# cpu.net
KiCad netlist of a schematic drawn in Altium Designer
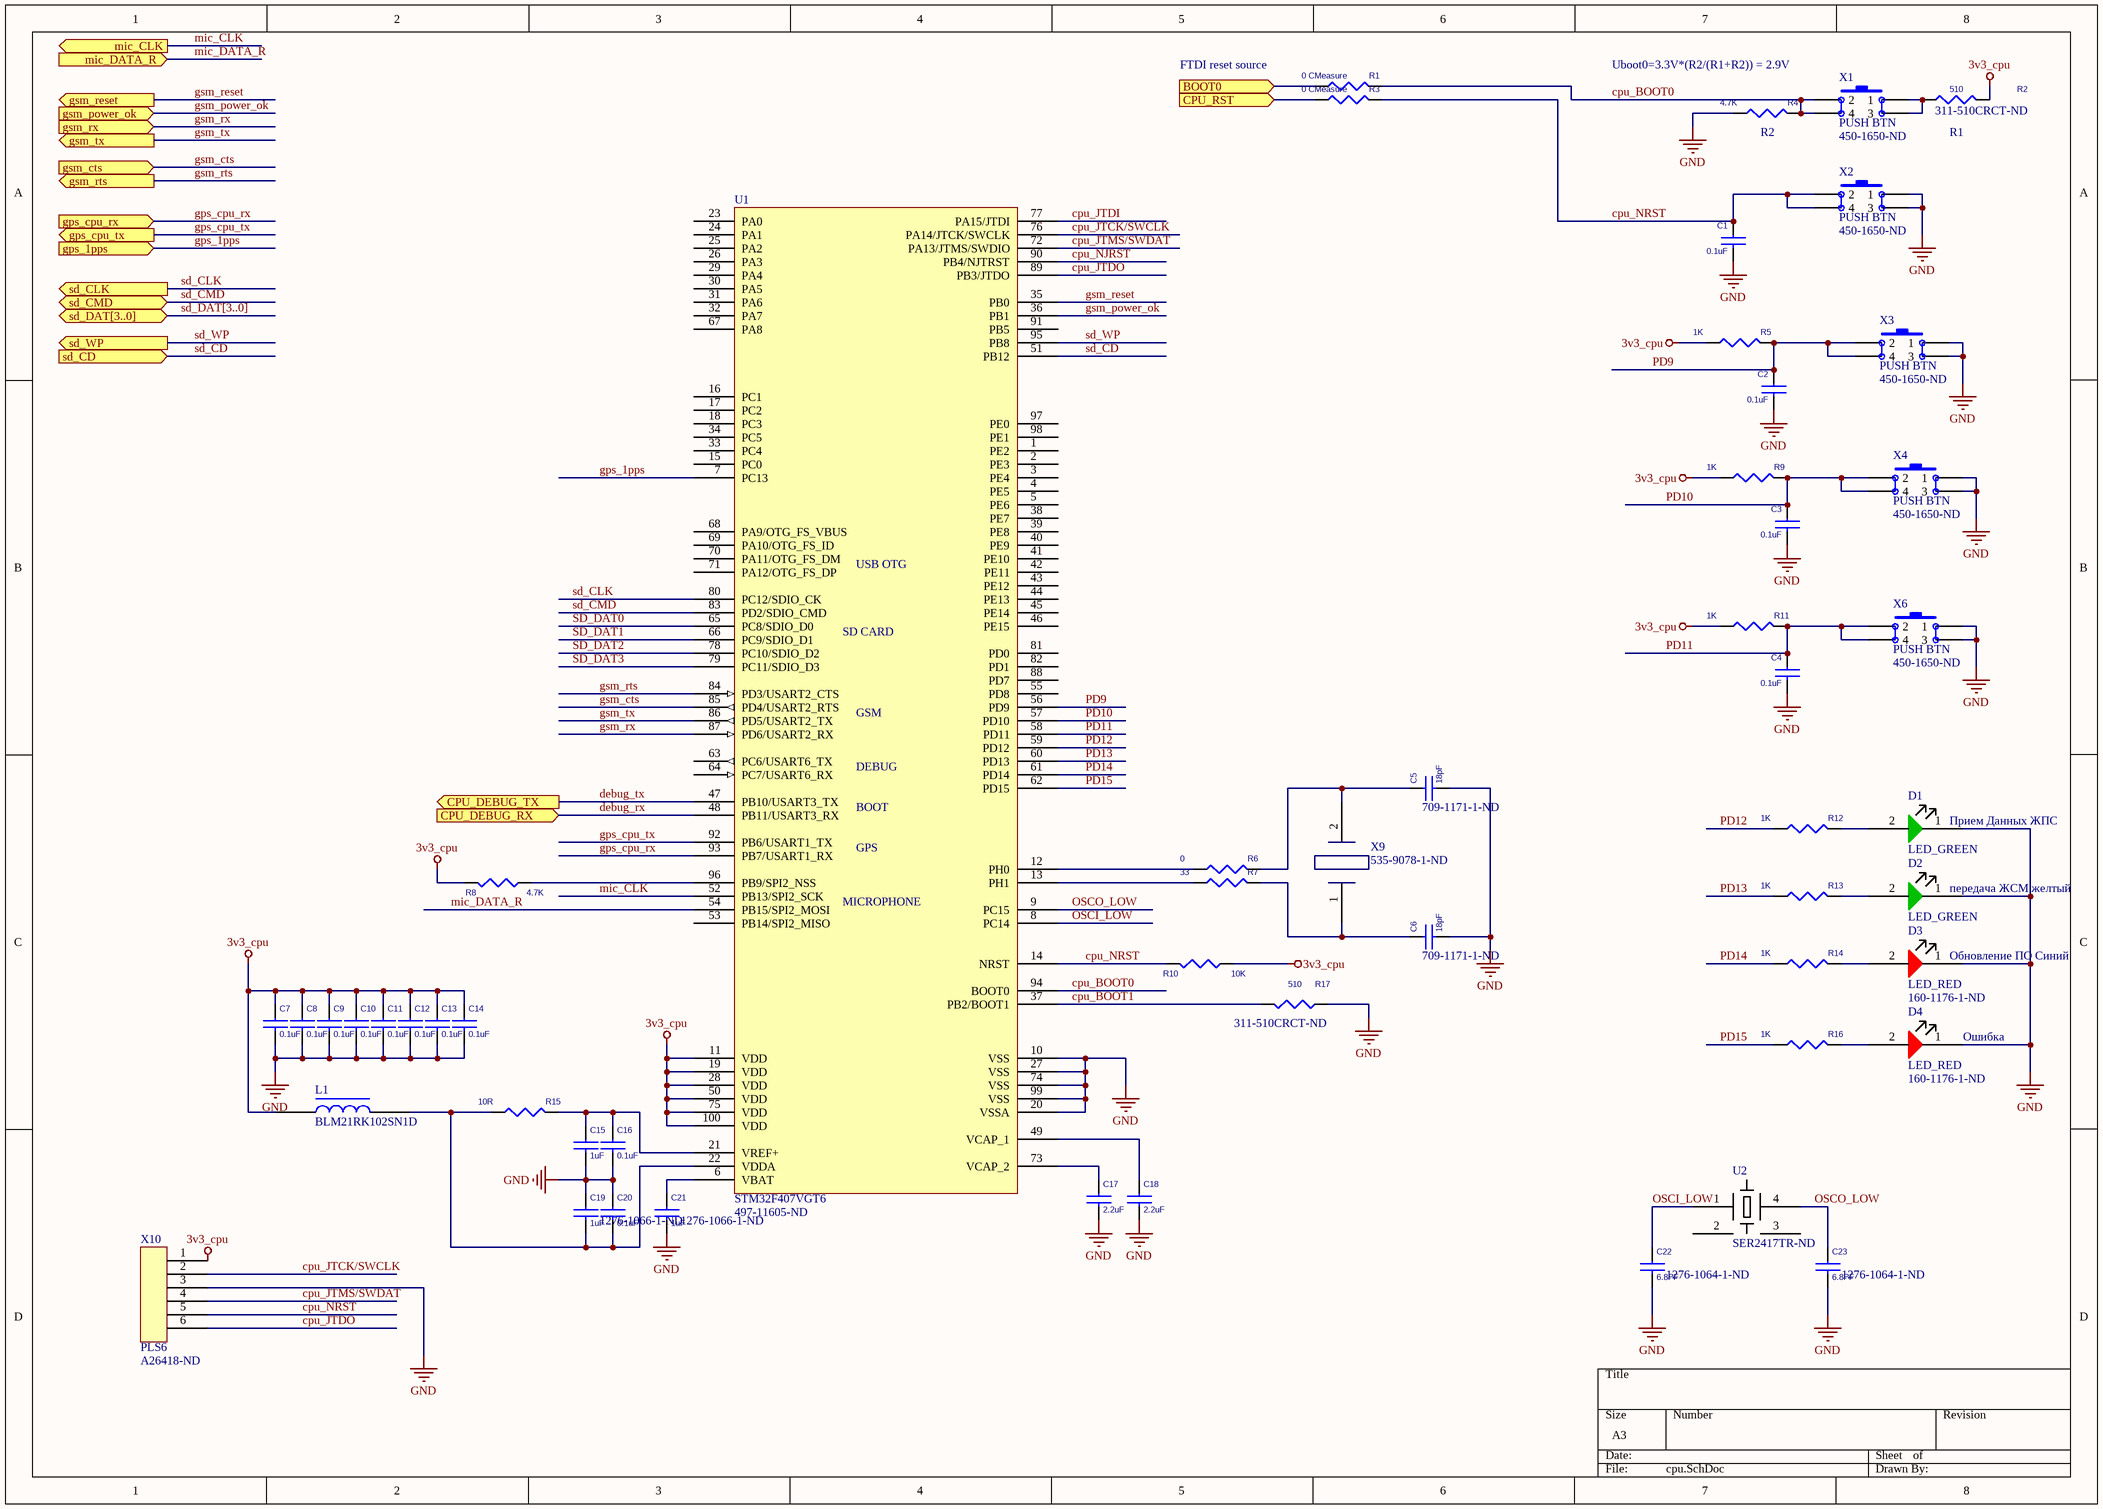
[diagram p0: cpu.SchDoc]

(export (version "E")
  (design (tool "Eeschema 10.0.6"))
  (components
    (comp (ref "C1")
      (value "0.1uF")
      (footprint "CAPC2012X09M")
      (description "CAP CER 0.1UF 25V 10% X7R 0805")
      (libsource (lib "Capacitors") (part "CAP_SMD_0.1UF_10%"))
    )
    (comp (ref "C2")
      (value "0.1uF")
      (footprint "CAPC2012X09M")
      (description "CAP CER 0.1UF 25V 10% X7R 0805")
      (libsource (lib "Capacitors") (part "CAP_SMD_0.1UF_10%"))
    )
    (comp (ref "C3")
      (value "0.1uF")
      (footprint "CAPC2012X09M")
      (description "CAP CER 0.1UF 25V 10% X7R 0805")
      (libsource (lib "Capacitors") (part "CAP_SMD_0.1UF_10%"))
    )
    (comp (ref "C4")
      (value "0.1uF")
      (footprint "CAPC2012X09M")
      (description "CAP CER 0.1UF 25V 10% X7R 0805")
      (libsource (lib "Capacitors") (part "CAP_SMD_0.1UF_10%"))
    )
    (comp (ref "C5")
      (value "18pF")
      (footprint "CAPC2012X09M")
      (description "CAP CER 27PF 200V 5% NP0 0805")
      (fields (field (name "SUPPLIER PART NUMBER 1") "709-1171-1-ND"))
      (libsource (lib "Capacitors") (part "CAP_SMD_18PF_5%"))
    )
    (comp (ref "C6")
      (value "18pF")
      (footprint "CAPC2012X09M")
      (description "CAP CER 27PF 200V 5% NP0 0805")
      (fields (field (name "SUPPLIER PART NUMBER 1") "709-1171-1-ND"))
      (libsource (lib "Capacitors") (part "CAP_SMD_18PF_5%"))
    )
    (comp (ref "C7")
      (value "0.1uF")
      (footprint "CAPC2012X09M")
      (description "CAP CER 0.1UF 25V 10% X7R 0805")
      (libsource (lib "Capacitors") (part "CAP_SMD_0.1UF_10%"))
    )
    (comp (ref "C8")
      (value "0.1uF")
      (footprint "CAPC2012X09M")
      (description "CAP CER 0.1UF 25V 10% X7R 0805")
      (libsource (lib "Capacitors") (part "CAP_SMD_0.1UF_10%"))
    )
    (comp (ref "C9")
      (value "0.1uF")
      (footprint "CAPC2012X09M")
      (description "CAP CER 0.1UF 25V 10% X7R 0805")
      (libsource (lib "Capacitors") (part "CAP_SMD_0.1UF_10%"))
    )
    (comp (ref "C10")
      (value "0.1uF")
      (footprint "CAPC2012X09M")
      (description "CAP CER 0.1UF 25V 10% X7R 0805")
      (libsource (lib "Capacitors") (part "CAP_SMD_0.1UF_10%"))
    )
    (comp (ref "C11")
      (value "0.1uF")
      (footprint "CAPC2012X09M")
      (description "CAP CER 0.1UF 25V 10% X7R 0805")
      (libsource (lib "Capacitors") (part "CAP_SMD_0.1UF_10%"))
    )
    (comp (ref "C12")
      (value "0.1uF")
      (footprint "CAPC2012X09M")
      (description "CAP CER 0.1UF 25V 10% X7R 0805")
      (libsource (lib "Capacitors") (part "CAP_SMD_0.1UF_10%"))
    )
    (comp (ref "C13")
      (value "0.1uF")
      (footprint "CAPC2012X09M")
      (description "CAP CER 0.1UF 25V 10% X7R 0805")
      (libsource (lib "Capacitors") (part "CAP_SMD_0.1UF_10%"))
    )
    (comp (ref "C14")
      (value "0.1uF")
      (footprint "CAPC2012X09M")
      (description "CAP CER 0.1UF 25V 10% X7R 0805")
      (libsource (lib "Capacitors") (part "CAP_SMD_0.1UF_10%"))
    )
    (comp (ref "C15")
      (value "1uF")
      (footprint "CAPC2012X09M")
      (description "MLCC; 1uF; 25V; X7R; ±10%; SMD; 0805;")
      (libsource (lib "Capacitors") (part "CAP_SMD_1uF_10%"))
    )
    (comp (ref "C16")
      (value "0.1uF")
      (footprint "CAPC2012X09M")
      (description "CAP CER 0.1UF 25V 10% X7R 0805")
      (libsource (lib "Capacitors") (part "CAP_SMD_0.1UF_10%"))
    )
    (comp (ref "C17")
      (value "2.2uF")
      (footprint "CAPC2012X09M")
      (description "CAP CER 2.2UF 16V 10% X5R 0805")
      (libsource (lib "Capacitors") (part "CAP_SMD_2.2uF_10%"))
    )
    (comp (ref "C18")
      (value "2.2uF")
      (footprint "CAPC2012X09M")
      (description "CAP CER 2.2UF 16V 10% X5R 0805")
      (libsource (lib "Capacitors") (part "CAP_SMD_2.2uF_10%"))
    )
    (comp (ref "C19")
      (value "1uF")
      (footprint "CAPC2012X09M")
      (description "MLCC; 1uF; 25V; X7R; ±10%; SMD; 0805;")
      (fields (field (name "SUPPLIER PART NUMBER 1") "1276-1066-1-ND"))
      (libsource (lib "Capacitors") (part "CAP_SMD_1uF_10%"))
    )
    (comp (ref "C20")
      (value "0.1uF")
      (footprint "CAPC2012X09M")
      (description "CAP CER 0.1UF 25V 10% X7R 0805")
      (libsource (lib "Capacitors") (part "CAP_SMD_0.1UF_10%"))
    )
    (comp (ref "C21")
      (value "1uF")
      (footprint "CAPC2012X09M")
      (description "MLCC; 1uF; 25V; X7R; ±10%; SMD; 0805;")
      (fields (field (name "SUPPLIER PART NUMBER 1") "1276-1066-1-ND"))
      (libsource (lib "Capacitors") (part "CAP_SMD_1uF_10%"))
    )
    (comp (ref "C22")
      (value "6.8PF")
      (footprint "CAPC2012X09M")
      (description "CAP MLCC 6.8PF 50V 5% NP0 0805")
      (fields (field (name "SUPPLIER PART NUMBER 1") "1276-1064-1-ND"))
      (libsource (lib "Capacitors") (part "CAP_SMD_6.8PF_5%"))
    )
    (comp (ref "C23")
      (value "6.8PF")
      (footprint "CAPC2012X09M")
      (description "CAP MLCC 6.8PF 50V 5% NP0 0805")
      (fields (field (name "SUPPLIER PART NUMBER 1") "1276-1064-1-ND"))
      (libsource (lib "Capacitors") (part "CAP_SMD_6.8PF_5%"))
    )
    (comp (ref "D1")
      (value "LED_GREEN")
      (footprint "DIOC2012X11N")
      (libsource (lib "Passive") (part "LED_GREEN"))
    )
    (comp (ref "D2")
      (value "LED_GREEN")
      (footprint "DIOC2012X11N")
      (libsource (lib "Passive") (part "LED_GREEN"))
    )
    (comp (ref "D3")
      (value "LED_RED")
      (footprint "DIOC2012X11N")
      (fields (field (name "SUPPLIER PART NUMBER 1") "160-1176-1-ND"))
      (libsource (lib "Passive") (part "LED_RED"))
    )
    (comp (ref "D4")
      (value "LED_RED")
      (footprint "DIOC2012X11N")
      (fields (field (name "SUPPLIER PART NUMBER 1") "160-1176-1-ND"))
      (libsource (lib "Passive") (part "LED_RED"))
    )
    (comp (ref "L1")
      (value "BLM21RK102SN1D")
      (footprint "DIOC2012X11N")
      (libsource (lib "Passive") (part "BLM21RK102SN1D"))
    )
    (comp (ref "R1")
      (value "0 CMeasure")
      (footprint "RESC2013X06M_CMEASURE")
      (description "RES 0.0 OHM 1/8W JUMP 0805 SMD")
      (libsource (lib "Resistors") (part "RES_SMD_0_CURRENT"))
    )
    (comp (ref "R2")
      (value "510")
      (footprint "RESC2013X06M")
      (description "RES - 510 OHM, 5%, 1/8W, 0805 SMD")
      (fields (field (name "SUPPLIER PART NUMBER 1") "311-510CRCT-ND"))
      (libsource (lib "Resistors") (part "RES_SMD_510_5%"))
    )
    (comp (ref "R3")
      (value "0 CMeasure")
      (footprint "RESC2013X06M_CMEASURE")
      (description "RES 0.0 OHM 1/8W JUMP 0805 SMD")
      (libsource (lib "Resistors") (part "RES_SMD_0_CURRENT"))
    )
    (comp (ref "R4")
      (value "4.7K")
      (footprint "RESC2013X06M")
      (description "RES 4.7K OHM 1/8W 1% 0805 SMD")
      (libsource (lib "Resistors") (part "RES_SMD_4.7K_1%"))
    )
    (comp (ref "R5")
      (value "1K")
      (footprint "RESC2013X06M")
      (description "RES - 1K OHM, 5%, 1/8W, 0805 SMD")
      (libsource (lib "Resistors") (part "RES_SMD_1K_5%"))
    )
    (comp (ref "R6")
      (value "0")
      (footprint "RESC2013X06M")
      (description "RES 0.0 OHM 1/8W JUMP 0805 SMD")
      (libsource (lib "Resistors") (part "RES_SMD_0"))
    )
    (comp (ref "R7")
      (value "33")
      (footprint "RESC2013X06M")
      (description "RES - 33 OHM, 5%, 1/8W, 0805 SMD")
      (libsource (lib "Resistors") (part "RES_SMD_33R_5%"))
    )
    (comp (ref "R8")
      (value "4.7K")
      (footprint "RESC2013X06M")
      (description "RES 4.7K OHM 1/8W 1% 0805 SMD")
      (libsource (lib "Resistors") (part "RES_SMD_4.7K_1%"))
    )
    (comp (ref "R9")
      (value "1K")
      (footprint "RESC2013X06M")
      (description "RES - 1K OHM, 5%, 1/8W, 0805 SMD")
      (libsource (lib "Resistors") (part "RES_SMD_1K_5%"))
    )
    (comp (ref "R10")
      (value "10K")
      (footprint "RESC2013X06M")
      (description "RES 10K OHM 1/8W 5% 0805 SMD")
      (libsource (lib "Resistors") (part "RES_SMD_10K_5%"))
    )
    (comp (ref "R11")
      (value "1K")
      (footprint "RESC2013X06M")
      (description "RES - 1K OHM, 5%, 1/8W, 0805 SMD")
      (libsource (lib "Resistors") (part "RES_SMD_1K_5%"))
    )
    (comp (ref "R12")
      (value "1K")
      (footprint "RESC2013X06M")
      (description "RES - 1K OHM, 5%, 1/8W, 0805 SMD")
      (libsource (lib "Resistors") (part "RES_SMD_1K_5%"))
    )
    (comp (ref "R13")
      (value "1K")
      (footprint "RESC2013X06M")
      (description "RES - 1K OHM, 5%, 1/8W, 0805 SMD")
      (libsource (lib "Resistors") (part "RES_SMD_1K_5%"))
    )
    (comp (ref "R14")
      (value "1K")
      (footprint "RESC2013X06M")
      (description "RES - 1K OHM, 5%, 1/8W, 0805 SMD")
      (libsource (lib "Resistors") (part "RES_SMD_1K_5%"))
    )
    (comp (ref "R15")
      (value "10R")
      (footprint "RESC2013X06M")
      (description "RES 10 OHM 1/8W 1% 0805 SMD")
      (libsource (lib "Resistors") (part "RES_SMD_10R_5%"))
    )
    (comp (ref "R16")
      (value "1K")
      (footprint "RESC2013X06M")
      (description "RES - 1K OHM, 5%, 1/8W, 0805 SMD")
      (libsource (lib "Resistors") (part "RES_SMD_1K_5%"))
    )
    (comp (ref "R17")
      (value "510")
      (footprint "RESC2013X06M")
      (description "RES - 510 OHM, 5%, 1/8W, 0805 SMD")
      (fields (field (name "SUPPLIER PART NUMBER 1") "311-510CRCT-ND"))
      (libsource (lib "Resistors") (part "RES_SMD_510_5%"))
    )
    (comp (ref "U1")
      (value "STM32F407VGT6")
      (footprint "TSQFP50P1600X1600X160-100M")
      (fields (field (name "SUPPLIER PART NUMBER 1") "497-11605-ND"))
      (libsource (lib "TruthEar") (part "STM32F407VGT6"))
    )
    (comp (ref "U2")
      (value "32.768KHZ")
      (footprint "SOJ550P380X254-4M")
      (fields (field (name "SUPPLIER PART NUMBER 1") "SER2417TR-ND"))
      (libsource (lib "TruthEar") (part "MC-306"))
    )
    (comp (ref "X1")
      (value "PUSH BTN")
      (footprint "PUSHBTN")
      (fields (field (name "SUPPLIER PART NUMBER 1") "450-1650-ND"))
      (libsource (lib "TruthEar") (part "SW1"))
    )
    (comp (ref "X2")
      (value "PUSH BTN")
      (footprint "PUSHBTN")
      (fields (field (name "SUPPLIER PART NUMBER 1") "450-1650-ND"))
      (libsource (lib "TruthEar") (part "SW1"))
    )
    (comp (ref "X3")
      (value "PUSH BTN")
      (footprint "PUSHBTN")
      (fields (field (name "SUPPLIER PART NUMBER 1") "450-1650-ND"))
      (libsource (lib "TruthEar") (part "SW1"))
    )
    (comp (ref "X4")
      (value "PUSH BTN")
      (footprint "PUSHBTN")
      (fields (field (name "SUPPLIER PART NUMBER 1") "450-1650-ND"))
      (libsource (lib "TruthEar") (part "SW1"))
    )
    (comp (ref "X6")
      (value "PUSH BTN")
      (footprint "PUSHBTN")
      (fields (field (name "SUPPLIER PART NUMBER 1") "450-1650-ND"))
      (libsource (lib "TruthEar") (part "SW1"))
    )
    (comp (ref "X9")
      (value "25.000Mhz")
      (footprint "SODFL1270X420-2L")
      (fields (field (name "SUPPLIER PART NUMBER 1") "535-9078-1-ND"))
      (libsource (lib "TruthEar") (part "OSC25M"))
    )
    (comp (ref "X10")
      (value "PLS6")
      (footprint "PLS6")
      (fields (field (name "SUPPLIER PART NUMBER 1") "A26418-ND"))
      (libsource (lib "Connectors") (part "PLS6"))
    )
  )
  (nets
    (net (code "5") (name "/BOOT0") (class "Default")
      (node (ref "R1") (pin "1") (pinfunction "1_1") (pintype "passive"))
    )
    (net (code "6") (name "/CPU_RST") (class "Default")
      (node (ref "R3") (pin "1") (pinfunction "1_1") (pintype "passive"))
    )
    (net (code "7") (name "/OSCI_LOW") (class "Default")
      (node (ref "C22") (pin "1") (pinfunction "1_1") (pintype "passive"))
      (node (ref "U1") (pin "8") (pinfunction "PC14_8") (pintype "passive"))
      (node (ref "U2") (pin "1") (pinfunction "OSC1_1") (pintype "power_in"))
    )
    (net (code "8") (name "/OSCO_LOW") (class "Default")
      (node (ref "C23") (pin "1") (pinfunction "1_1") (pintype "passive"))
      (node (ref "U1") (pin "9") (pinfunction "PC15_9") (pintype "passive"))
      (node (ref "U2") (pin "4") (pinfunction "OSC2_4") (pintype "power_in"))
    )
    (net (code "9") (name "/PD9") (class "Default")
      (node (ref "C2") (pin "1") (pinfunction "1_1") (pintype "passive"))
      (node (ref "R5") (pin "2") (pinfunction "2_2") (pintype "passive"))
      (node (ref "U1") (pin "56") (pinfunction "PD9_56") (pintype "passive"))
      (node (ref "X3") (pin "2") (pinfunction "2_2") (pintype "passive"))
      (node (ref "X3") (pin "4") (pinfunction "4_4") (pintype "passive"))
    )
    (net (code "10") (name "/PD10") (class "Default")
      (node (ref "C3") (pin "1") (pinfunction "1_1") (pintype "passive"))
      (node (ref "R9") (pin "2") (pinfunction "2_2") (pintype "passive"))
      (node (ref "U1") (pin "57") (pinfunction "PD10_57") (pintype "passive"))
      (node (ref "X4") (pin "2") (pinfunction "2_2") (pintype "passive"))
      (node (ref "X4") (pin "4") (pinfunction "4_4") (pintype "passive"))
    )
    (net (code "11") (name "/PD11") (class "Default")
      (node (ref "C4") (pin "1") (pinfunction "1_1") (pintype "passive"))
      (node (ref "R11") (pin "2") (pinfunction "2_2") (pintype "passive"))
      (node (ref "U1") (pin "58") (pinfunction "PD11_58") (pintype "passive"))
      (node (ref "X6") (pin "2") (pinfunction "2_2") (pintype "passive"))
      (node (ref "X6") (pin "4") (pinfunction "4_4") (pintype "passive"))
    )
    (net (code "12") (name "/PD12") (class "Default")
      (node (ref "R12") (pin "1") (pinfunction "1_1") (pintype "passive"))
      (node (ref "U1") (pin "59") (pinfunction "PD12_59") (pintype "passive"))
    )
    (net (code "13") (name "/PD13") (class "Default")
      (node (ref "R13") (pin "1") (pinfunction "1_1") (pintype "passive"))
      (node (ref "U1") (pin "60") (pinfunction "PD13_60") (pintype "passive"))
    )
    (net (code "14") (name "/PD14") (class "Default")
      (node (ref "R14") (pin "1") (pinfunction "1_1") (pintype "passive"))
      (node (ref "U1") (pin "61") (pinfunction "PD14_61") (pintype "passive"))
    )
    (net (code "15") (name "/PD15") (class "Default")
      (node (ref "R16") (pin "1") (pinfunction "1_1") (pintype "passive"))
      (node (ref "U1") (pin "62") (pinfunction "PD15_62") (pintype "passive"))
    )
    (net (code "16") (name "/SD_DAT0") (class "Default")
      (node (ref "U1") (pin "65") (pinfunction "PC8/SDIO_D0_65") (pintype "passive"))
    )
    (net (code "17") (name "/SD_DAT1") (class "Default")
      (node (ref "U1") (pin "66") (pinfunction "PC9/SDIO_D1_66") (pintype "passive"))
    )
    (net (code "18") (name "/SD_DAT2") (class "Default")
      (node (ref "U1") (pin "78") (pinfunction "PC10/SDIO_D2_78") (pintype "passive"))
    )
    (net (code "19") (name "/SD_DAT3") (class "Default")
      (node (ref "U1") (pin "79") (pinfunction "PC11/SDIO_D3_79") (pintype "passive"))
    )
    (net (code "20") (name "/cpu_BOOT0") (class "Default")
      (node (ref "R1") (pin "2") (pinfunction "2_2") (pintype "passive"))
      (node (ref "R4") (pin "2") (pinfunction "2_2") (pintype "passive"))
      (node (ref "U1") (pin "94") (pinfunction "BOOT0_94") (pintype "passive"))
      (node (ref "X1") (pin "2") (pinfunction "2_2") (pintype "passive"))
      (node (ref "X1") (pin "4") (pinfunction "4_4") (pintype "passive"))
    )
    (net (code "21") (name "/cpu_BOOT1") (class "Default")
      (node (ref "R17") (pin "2") (pinfunction "2_2") (pintype "passive"))
      (node (ref "U1") (pin "37") (pinfunction "PB2/BOOT1_37") (pintype "passive"))
    )
    (net (code "22") (name "/cpu_JTCK{slash}SWCLK") (class "Default")
      (node (ref "U1") (pin "76") (pinfunction "PA14/JTCK/SWCLK_76") (pintype "passive"))
      (node (ref "X10") (pin "2") (pinfunction "2_2") (pintype "power_in"))
    )
    (net (code "23") (name "/cpu_JTDI") (class "Default")
      (node (ref "U1") (pin "77") (pinfunction "PA15/JTDI_77") (pintype "passive"))
    )
    (net (code "24") (name "/cpu_JTDO") (class "Default")
      (node (ref "U1") (pin "89") (pinfunction "PB3/JTDO_89") (pintype "passive"))
      (node (ref "X10") (pin "6") (pinfunction "6_6") (pintype "power_in"))
    )
    (net (code "25") (name "/cpu_JTMS{slash}SWDAT") (class "Default")
      (node (ref "U1") (pin "72") (pinfunction "PA13/JTMS/SWDIO_72") (pintype "passive"))
      (node (ref "X10") (pin "4") (pinfunction "4_4") (pintype "power_in"))
    )
    (net (code "26") (name "/cpu_NJRST") (class "Default")
      (node (ref "U1") (pin "90") (pinfunction "PB4/NJTRST_90") (pintype "passive"))
    )
    (net (code "27") (name "/cpu_NRST") (class "Default")
      (node (ref "C1") (pin "1") (pinfunction "1_1") (pintype "passive"))
      (node (ref "R10") (pin "2") (pinfunction "2_2") (pintype "passive"))
      (node (ref "R3") (pin "2") (pinfunction "2_2") (pintype "passive"))
      (node (ref "U1") (pin "14") (pinfunction "NRST_14") (pintype "passive"))
      (node (ref "X10") (pin "5") (pinfunction "5_5") (pintype "power_in"))
      (node (ref "X2") (pin "2") (pinfunction "2_2") (pintype "passive"))
      (node (ref "X2") (pin "4") (pinfunction "4_4") (pintype "passive"))
    )
    (net (code "28") (name "/debug_rx") (class "Default")
      (node (ref "U1") (pin "48") (pinfunction "PB11/USART3_RX_48") (pintype "passive"))
    )
    (net (code "29") (name "/debug_tx") (class "Default")
      (node (ref "U1") (pin "47") (pinfunction "PB10/USART3_TX_47") (pintype "passive"))
    )
    (net (code "30") (name "/gps_1pps") (class "Default")
      (node (ref "U1") (pin "7") (pinfunction "PC13_7") (pintype "passive"))
    )
    (net (code "31") (name "/gps_cpu_rx") (class "Default")
      (node (ref "U1") (pin "93") (pinfunction "PB7/USART1_RX_93") (pintype "passive"))
    )
    (net (code "32") (name "/gps_cpu_tx") (class "Default")
      (node (ref "U1") (pin "92") (pinfunction "PB6/USART1_TX_92") (pintype "passive"))
    )
    (net (code "33") (name "/gsm_cts") (class "Default")
      (node (ref "U1") (pin "85") (pinfunction "PD4/USART2_RTS_85") (pintype "output"))
    )
    (net (code "34") (name "/gsm_power_ok") (class "Default")
      (node (ref "U1") (pin "36") (pinfunction "PB1_36") (pintype "passive"))
    )
    (net (code "35") (name "/gsm_reset") (class "Default")
      (node (ref "U1") (pin "35") (pinfunction "PB0_35") (pintype "passive"))
    )
    (net (code "36") (name "/gsm_rts") (class "Default")
      (node (ref "U1") (pin "84") (pinfunction "PD3/USART2_CTS_84") (pintype "input"))
    )
    (net (code "37") (name "/gsm_rx") (class "Default")
      (node (ref "U1") (pin "87") (pinfunction "PD6/USART2_RX_87") (pintype "input"))
    )
    (net (code "38") (name "/gsm_tx") (class "Default")
      (node (ref "U1") (pin "86") (pinfunction "PD5/USART2_TX_86") (pintype "output"))
    )
    (net (code "39") (name "/mic_CLK") (class "Default")
      (node (ref "U1") (pin "52") (pinfunction "PB13/SPI2_SCK_52") (pintype "passive"))
    )
    (net (code "40") (name "/mic_DATA_R") (class "Default")
      (node (ref "U1") (pin "54") (pinfunction "PB15/SPI2_MOSI_54") (pintype "passive"))
    )
    (net (code "41") (name "/sd_CD") (class "Default")
      (node (ref "U1") (pin "51") (pinfunction "PB12_51") (pintype "passive"))
    )
    (net (code "42") (name "/sd_CLK") (class "Default")
      (node (ref "U1") (pin "80") (pinfunction "PC12/SDIO_CK_80") (pintype "passive"))
    )
    (net (code "43") (name "/sd_CMD") (class "Default")
      (node (ref "U1") (pin "83") (pinfunction "PD2/SDIO_CMD_83") (pintype "passive"))
    )
    (net (code "45") (name "/sd_WP") (class "Default")
      (node (ref "U1") (pin "95") (pinfunction "PB8_95") (pintype "passive"))
    )
    (net (code "46") (name "3v3_cpu") (class "Default")
      (node (ref "C10") (pin "1") (pinfunction "1_1") (pintype "passive"))
      (node (ref "C11") (pin "1") (pinfunction "1_1") (pintype "passive"))
      (node (ref "C12") (pin "1") (pinfunction "1_1") (pintype "passive"))
      (node (ref "C13") (pin "1") (pinfunction "1_1") (pintype "passive"))
      (node (ref "C14") (pin "1") (pinfunction "1_1") (pintype "passive"))
      (node (ref "C7") (pin "1") (pinfunction "1_1") (pintype "passive"))
      (node (ref "C8") (pin "1") (pinfunction "1_1") (pintype "passive"))
      (node (ref "C9") (pin "1") (pinfunction "1_1") (pintype "passive"))
      (node (ref "L1") (pin "1") (pinfunction "1_1") (pintype "passive"))
      (node (ref "R10") (pin "1") (pinfunction "1_1") (pintype "passive"))
      (node (ref "R11") (pin "1") (pinfunction "1_1") (pintype "passive"))
      (node (ref "R2") (pin "1") (pinfunction "1_1") (pintype "passive"))
      (node (ref "R5") (pin "1") (pinfunction "1_1") (pintype "passive"))
      (node (ref "R8") (pin "2") (pinfunction "2_2") (pintype "passive"))
      (node (ref "R9") (pin "1") (pinfunction "1_1") (pintype "passive"))
      (node (ref "U1") (pin "100") (pinfunction "VDD_100") (pintype "passive"))
      (node (ref "U1") (pin "11") (pinfunction "VDD_11") (pintype "passive"))
      (node (ref "U1") (pin "19") (pinfunction "VDD_19") (pintype "passive"))
      (node (ref "U1") (pin "28") (pinfunction "VDD_28") (pintype "passive"))
      (node (ref "U1") (pin "50") (pinfunction "VDD_50") (pintype "passive"))
      (node (ref "U1") (pin "75") (pinfunction "VDD_75") (pintype "passive"))
      (node (ref "X10") (pin "1") (pinfunction "1_1") (pintype "power_in"))
    )
    (net (code "47") (name "GND") (class "Default")
      (node (ref "C1") (pin "2") (pinfunction "2_2") (pintype "passive"))
      (node (ref "C10") (pin "2") (pinfunction "2_2") (pintype "passive"))
      (node (ref "C11") (pin "2") (pinfunction "2_2") (pintype "passive"))
      (node (ref "C12") (pin "2") (pinfunction "2_2") (pintype "passive"))
      (node (ref "C13") (pin "2") (pinfunction "2_2") (pintype "passive"))
      (node (ref "C14") (pin "2") (pinfunction "2_2") (pintype "passive"))
      (node (ref "C15") (pin "2") (pinfunction "2_2") (pintype "passive"))
      (node (ref "C16") (pin "2") (pinfunction "2_2") (pintype "passive"))
      (node (ref "C17") (pin "2") (pinfunction "2_2") (pintype "passive"))
      (node (ref "C18") (pin "2") (pinfunction "2_2") (pintype "passive"))
      (node (ref "C19") (pin "1") (pinfunction "1_1") (pintype "passive"))
      (node (ref "C2") (pin "2") (pinfunction "2_2") (pintype "passive"))
      (node (ref "C20") (pin "1") (pinfunction "1_1") (pintype "passive"))
      (node (ref "C21") (pin "2") (pinfunction "2_2") (pintype "passive"))
      (node (ref "C22") (pin "2") (pinfunction "2_2") (pintype "passive"))
      (node (ref "C23") (pin "2") (pinfunction "2_2") (pintype "passive"))
      (node (ref "C3") (pin "2") (pinfunction "2_2") (pintype "passive"))
      (node (ref "C4") (pin "2") (pinfunction "2_2") (pintype "passive"))
      (node (ref "C5") (pin "2") (pinfunction "2_2") (pintype "passive"))
      (node (ref "C6") (pin "2") (pinfunction "2_2") (pintype "passive"))
      (node (ref "C7") (pin "2") (pinfunction "2_2") (pintype "passive"))
      (node (ref "C8") (pin "2") (pinfunction "2_2") (pintype "passive"))
      (node (ref "C9") (pin "2") (pinfunction "2_2") (pintype "passive"))
      (node (ref "D1") (pin "1") (pinfunction "C_1") (pintype "passive"))
      (node (ref "D2") (pin "1") (pinfunction "C_1") (pintype "passive"))
      (node (ref "D3") (pin "1") (pinfunction "C_1") (pintype "passive"))
      (node (ref "D4") (pin "1") (pinfunction "C_1") (pintype "passive"))
      (node (ref "R17") (pin "1") (pinfunction "1_1") (pintype "passive"))
      (node (ref "R4") (pin "1") (pinfunction "1_1") (pintype "passive"))
      (node (ref "U1") (pin "10") (pinfunction "VSS_10") (pintype "passive"))
      (node (ref "U1") (pin "20") (pinfunction "VSSA_20") (pintype "passive"))
      (node (ref "U1") (pin "27") (pinfunction "VSS_27") (pintype "passive"))
      (node (ref "U1") (pin "74") (pinfunction "VSS_74") (pintype "passive"))
      (node (ref "U1") (pin "99") (pinfunction "VSS_99") (pintype "passive"))
      (node (ref "X10") (pin "3") (pinfunction "3_3") (pintype "power_in"))
      (node (ref "X2") (pin "1") (pinfunction "1_1") (pintype "passive"))
      (node (ref "X2") (pin "3") (pinfunction "3_3") (pintype "passive"))
      (node (ref "X3") (pin "1") (pinfunction "1_1") (pintype "passive"))
      (node (ref "X3") (pin "3") (pinfunction "3_3") (pintype "passive"))
      (node (ref "X4") (pin "1") (pinfunction "1_1") (pintype "passive"))
      (node (ref "X4") (pin "3") (pinfunction "3_3") (pintype "passive"))
      (node (ref "X6") (pin "1") (pinfunction "1_1") (pintype "passive"))
      (node (ref "X6") (pin "3") (pinfunction "3_3") (pintype "passive"))
    )
    (net (code "48") (name "Net-(C5-Pad1)") (class "Default")
      (node (ref "C5") (pin "1") (pinfunction "1_1") (pintype "passive"))
      (node (ref "R6") (pin "2") (pinfunction "2_2") (pintype "passive"))
      (node (ref "X9") (pin "2") (pinfunction "2_2") (pintype "power_in"))
    )
    (net (code "49") (name "Net-(C6-Pad1)") (class "Default")
      (node (ref "C6") (pin "1") (pinfunction "1_1") (pintype "passive"))
      (node (ref "R7") (pin "2") (pinfunction "2_2") (pintype "passive"))
      (node (ref "X9") (pin "1") (pinfunction "1_1") (pintype "power_in"))
    )
    (net (code "50") (name "Net-(D1-A)") (class "Default")
      (node (ref "D1") (pin "2") (pinfunction "A_2") (pintype "passive"))
      (node (ref "R12") (pin "2") (pinfunction "2_2") (pintype "passive"))
    )
    (net (code "51") (name "Net-(D2-A)") (class "Default")
      (node (ref "D2") (pin "2") (pinfunction "A_2") (pintype "passive"))
      (node (ref "R13") (pin "2") (pinfunction "2_2") (pintype "passive"))
    )
    (net (code "52") (name "Net-(D3-A)") (class "Default")
      (node (ref "D3") (pin "2") (pinfunction "A_2") (pintype "passive"))
      (node (ref "R14") (pin "2") (pinfunction "2_2") (pintype "passive"))
    )
    (net (code "53") (name "Net-(D4-A)") (class "Default")
      (node (ref "D4") (pin "2") (pinfunction "A_2") (pintype "passive"))
      (node (ref "R16") (pin "2") (pinfunction "2_2") (pintype "passive"))
    )
    (net (code "54") (name "Net-(R2-Pad2)") (class "Default")
      (node (ref "R2") (pin "2") (pinfunction "2_2") (pintype "passive"))
      (node (ref "X1") (pin "1") (pinfunction "1_1") (pintype "passive"))
      (node (ref "X1") (pin "3") (pinfunction "3_3") (pintype "passive"))
    )
    (net (code "55") (name "Net-(U1-PB9{slash}SPI2_NSS)") (class "Default")
      (node (ref "R8") (pin "1") (pinfunction "1_1") (pintype "passive"))
      (node (ref "U1") (pin "96") (pinfunction "PB9/SPI2_NSS_96") (pintype "passive"))
    )
    (net (code "56") (name "Net-(U1-PH0)") (class "Default")
      (node (ref "R6") (pin "1") (pinfunction "1_1") (pintype "passive"))
      (node (ref "U1") (pin "12") (pinfunction "PH0_12") (pintype "passive"))
    )
    (net (code "57") (name "Net-(U1-PH1)") (class "Default")
      (node (ref "R7") (pin "1") (pinfunction "1_1") (pintype "passive"))
      (node (ref "U1") (pin "13") (pinfunction "PH1_13") (pintype "passive"))
    )
    (net (code "58") (name "Net-(U1-VBAT)") (class "Default")
      (node (ref "C21") (pin "1") (pinfunction "1_1") (pintype "passive"))
      (node (ref "U1") (pin "6") (pinfunction "VBAT_6") (pintype "passive"))
    )
    (net (code "59") (name "Net-(U1-VCAP_1)") (class "Default")
      (node (ref "C18") (pin "1") (pinfunction "1_1") (pintype "passive"))
      (node (ref "U1") (pin "49") (pinfunction "VCAP_1_49") (pintype "passive"))
    )
    (net (code "60") (name "Net-(U1-VCAP_2)") (class "Default")
      (node (ref "C17") (pin "1") (pinfunction "1_1") (pintype "passive"))
      (node (ref "U1") (pin "73") (pinfunction "VCAP_2_73") (pintype "passive"))
    )
    (net (code "61") (name "Net-(U1-VDDA)") (class "Default")
      (node (ref "C19") (pin "2") (pinfunction "2_2") (pintype "passive"))
      (node (ref "C20") (pin "2") (pinfunction "2_2") (pintype "passive"))
      (node (ref "L1") (pin "2") (pinfunction "2_2") (pintype "passive"))
      (node (ref "R15") (pin "1") (pinfunction "1_1") (pintype "passive"))
      (node (ref "U1") (pin "22") (pinfunction "VDDA_22") (pintype "passive"))
    )
    (net (code "62") (name "Net-(U1-VREF+)") (class "Default")
      (node (ref "C15") (pin "1") (pinfunction "1_1") (pintype "passive"))
      (node (ref "C16") (pin "1") (pinfunction "1_1") (pintype "passive"))
      (node (ref "R15") (pin "2") (pinfunction "2_2") (pintype "passive"))
      (node (ref "U1") (pin "21") (pinfunction "VREF+_21") (pintype "passive"))
    )
    (net (code "63") (name "unconnected-(U1-PA0-Pad23)") (class "Default")
      (node (ref "U1") (pin "23") (pinfunction "PA0_23") (pintype "passive"))
    )
    (net (code "64") (name "unconnected-(U1-PA1-Pad24)") (class "Default")
      (node (ref "U1") (pin "24") (pinfunction "PA1_24") (pintype "passive"))
    )
    (net (code "65") (name "unconnected-(U1-PA2-Pad25)") (class "Default")
      (node (ref "U1") (pin "25") (pinfunction "PA2_25") (pintype "passive"))
    )
    (net (code "66") (name "unconnected-(U1-PA3-Pad26)") (class "Default")
      (node (ref "U1") (pin "26") (pinfunction "PA3_26") (pintype "passive"))
    )
    (net (code "67") (name "unconnected-(U1-PA4-Pad29)") (class "Default")
      (node (ref "U1") (pin "29") (pinfunction "PA4_29") (pintype "passive"))
    )
    (net (code "68") (name "unconnected-(U1-PA5-Pad30)") (class "Default")
      (node (ref "U1") (pin "30") (pinfunction "PA5_30") (pintype "passive"))
    )
    (net (code "69") (name "unconnected-(U1-PA6-Pad31)") (class "Default")
      (node (ref "U1") (pin "31") (pinfunction "PA6_31") (pintype "passive"))
    )
    (net (code "70") (name "unconnected-(U1-PA7-Pad32)") (class "Default")
      (node (ref "U1") (pin "32") (pinfunction "PA7_32") (pintype "passive"))
    )
    (net (code "71") (name "unconnected-(U1-PA8-Pad67)") (class "Default")
      (node (ref "U1") (pin "67") (pinfunction "PA8_67") (pintype "passive"))
    )
    (net (code "72") (name "unconnected-(U1-PA9{slash}OTG_FS_VBUS-Pad68)") (class "Default")
      (node (ref "U1") (pin "68") (pinfunction "PA9/OTG_FS_VBUS_68") (pintype "passive"))
    )
    (net (code "73") (name "unconnected-(U1-PA10{slash}OTG_FS_ID-Pad69)") (class "Default")
      (node (ref "U1") (pin "69") (pinfunction "PA10/OTG_FS_ID_69") (pintype "passive"))
    )
    (net (code "74") (name "unconnected-(U1-PA11{slash}OTG_FS_DM-Pad70)") (class "Default")
      (node (ref "U1") (pin "70") (pinfunction "PA11/OTG_FS_DM_70") (pintype "passive"))
    )
    (net (code "75") (name "unconnected-(U1-PA12{slash}OTG_FS_DP-Pad71)") (class "Default")
      (node (ref "U1") (pin "71") (pinfunction "PA12/OTG_FS_DP_71") (pintype "passive"))
    )
    (net (code "76") (name "unconnected-(U1-PB5-Pad91)") (class "Default")
      (node (ref "U1") (pin "91") (pinfunction "PB5_91") (pintype "passive"))
    )
    (net (code "77") (name "unconnected-(U1-PB14{slash}SPI2_MISO-Pad53)") (class "Default")
      (node (ref "U1") (pin "53") (pinfunction "PB14/SPI2_MISO_53") (pintype "passive"))
    )
    (net (code "78") (name "unconnected-(U1-PC0-Pad15)") (class "Default")
      (node (ref "U1") (pin "15") (pinfunction "PC0_15") (pintype "passive"))
    )
    (net (code "79") (name "unconnected-(U1-PC1-Pad16)") (class "Default")
      (node (ref "U1") (pin "16") (pinfunction "PC1_16") (pintype "passive"))
    )
    (net (code "80") (name "unconnected-(U1-PC2-Pad17)") (class "Default")
      (node (ref "U1") (pin "17") (pinfunction "PC2_17") (pintype "passive"))
    )
    (net (code "81") (name "unconnected-(U1-PC3-Pad18)") (class "Default")
      (node (ref "U1") (pin "18") (pinfunction "PC3_18") (pintype "passive"))
    )
    (net (code "82") (name "unconnected-(U1-PC4-Pad33)") (class "Default")
      (node (ref "U1") (pin "33") (pinfunction "PC4_33") (pintype "passive"))
    )
    (net (code "83") (name "unconnected-(U1-PC5-Pad34)") (class "Default")
      (node (ref "U1") (pin "34") (pinfunction "PC5_34") (pintype "passive"))
    )
    (net (code "84") (name "unconnected-(U1-PC6{slash}USART6_TX-Pad63)") (class "Default")
      (node (ref "U1") (pin "63") (pinfunction "PC6/USART6_TX_63") (pintype "output"))
    )
    (net (code "85") (name "unconnected-(U1-PC7{slash}USART6_RX-Pad64)") (class "Default")
      (node (ref "U1") (pin "64") (pinfunction "PC7/USART6_RX_64") (pintype "input"))
    )
    (net (code "86") (name "unconnected-(U1-PD0-Pad81)") (class "Default")
      (node (ref "U1") (pin "81") (pinfunction "PD0_81") (pintype "passive"))
    )
    (net (code "87") (name "unconnected-(U1-PD1-Pad82)") (class "Default")
      (node (ref "U1") (pin "82") (pinfunction "PD1_82") (pintype "passive"))
    )
    (net (code "88") (name "unconnected-(U1-PD7-Pad88)") (class "Default")
      (node (ref "U1") (pin "88") (pinfunction "PD7_88") (pintype "passive"))
    )
    (net (code "89") (name "unconnected-(U1-PD8-Pad55)") (class "Default")
      (node (ref "U1") (pin "55") (pinfunction "PD8_55") (pintype "passive"))
    )
    (net (code "90") (name "unconnected-(U1-PE0-Pad97)") (class "Default")
      (node (ref "U1") (pin "97") (pinfunction "PE0_97") (pintype "passive"))
    )
    (net (code "91") (name "unconnected-(U1-PE1-Pad98)") (class "Default")
      (node (ref "U1") (pin "98") (pinfunction "PE1_98") (pintype "passive"))
    )
    (net (code "92") (name "unconnected-(U1-PE2-Pad1)") (class "Default")
      (node (ref "U1") (pin "1") (pinfunction "PE2_1") (pintype "passive"))
    )
    (net (code "93") (name "unconnected-(U1-PE3-Pad2)") (class "Default")
      (node (ref "U1") (pin "2") (pinfunction "PE3_2") (pintype "passive"))
    )
    (net (code "94") (name "unconnected-(U1-PE4-Pad3)") (class "Default")
      (node (ref "U1") (pin "3") (pinfunction "PE4_3") (pintype "passive"))
    )
    (net (code "95") (name "unconnected-(U1-PE5-Pad4)") (class "Default")
      (node (ref "U1") (pin "4") (pinfunction "PE5_4") (pintype "passive"))
    )
    (net (code "96") (name "unconnected-(U1-PE6-Pad5)") (class "Default")
      (node (ref "U1") (pin "5") (pinfunction "PE6_5") (pintype "passive"))
    )
    (net (code "97") (name "unconnected-(U1-PE7-Pad38)") (class "Default")
      (node (ref "U1") (pin "38") (pinfunction "PE7_38") (pintype "passive"))
    )
    (net (code "98") (name "unconnected-(U1-PE8-Pad39)") (class "Default")
      (node (ref "U1") (pin "39") (pinfunction "PE8_39") (pintype "passive"))
    )
    (net (code "99") (name "unconnected-(U1-PE9-Pad40)") (class "Default")
      (node (ref "U1") (pin "40") (pinfunction "PE9_40") (pintype "passive"))
    )
    (net (code "100") (name "unconnected-(U1-PE10-Pad41)") (class "Default")
      (node (ref "U1") (pin "41") (pinfunction "PE10_41") (pintype "passive"))
    )
    (net (code "101") (name "unconnected-(U1-PE11-Pad42)") (class "Default")
      (node (ref "U1") (pin "42") (pinfunction "PE11_42") (pintype "passive"))
    )
    (net (code "102") (name "unconnected-(U1-PE12-Pad43)") (class "Default")
      (node (ref "U1") (pin "43") (pinfunction "PE12_43") (pintype "passive"))
    )
    (net (code "103") (name "unconnected-(U1-PE13-Pad44)") (class "Default")
      (node (ref "U1") (pin "44") (pinfunction "PE13_44") (pintype "passive"))
    )
    (net (code "104") (name "unconnected-(U1-PE14-Pad45)") (class "Default")
      (node (ref "U1") (pin "45") (pinfunction "PE14_45") (pintype "passive"))
    )
    (net (code "105") (name "unconnected-(U1-PE15-Pad46)") (class "Default")
      (node (ref "U1") (pin "46") (pinfunction "PE15_46") (pintype "passive"))
    )
    (net (code "106") (name "unconnected-(U2-NC-Pad2)") (class "Default")
      (node (ref "U2") (pin "2") (pinfunction "NC_2") (pintype "power_in"))
    )
    (net (code "107") (name "unconnected-(U2-NC-Pad3)") (class "Default")
      (node (ref "U2") (pin "3") (pinfunction "NC_3") (pintype "power_in"))
    )
  )
)
